# 9250.net
KiCad netlist of a schematic drawn in Altium Designer
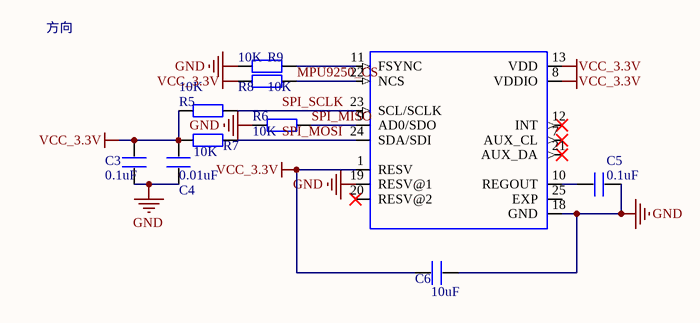
[diagram p0: 9250.SchDoc]

(export (version "E")
  (design (tool "Eeschema 10.0.6"))
  (components
    (comp (ref "C3") (value "0.1uF") (footprint "0805") (libsource (lib "OLED模块封装库") (part "C")))
    (comp (ref "C4") (value "0.01uF") (footprint "0805") (libsource (lib "OLED模块封装库") (part "C")))
    (comp (ref "C5") (value "0.1uF") (footprint "0805") (libsource (lib "OLED模块封装库") (part "C")))
    (comp (ref "C6") (value "10uF") (footprint "0805") (libsource (lib "OLED模块封装库") (part "C")))
    (comp (ref "R5")
      (value "10K")
      (footprint "3.5TFTLCD封装库:0805")
      (description "Resistor")
      (fields (field (name "Comment") "Res2") (field (name "PUBLISHER") "Altium Limited"))
      (libsource (lib "Miscellaneous Devices") (part "Res2"))
    )
    (comp (ref "R6")
      (value "10K")
      (footprint "3.5TFTLCD封装库:0805")
      (description "Resistor")
      (fields (field (name "Comment") "Res2") (field (name "PUBLISHER") "Altium Limited"))
      (libsource (lib "") (part "Res2_1"))
    )
    (comp (ref "R7")
      (value "10K")
      (footprint "3.5TFTLCD封装库:0805")
      (description "Resistor")
      (fields (field (name "Comment") "Res2") (field (name "PUBLISHER") "Altium Limited"))
      (libsource (lib "Miscellaneous Devices") (part "Res2"))
    )
    (comp (ref "R8")
      (value "10K")
      (footprint "3.5TFTLCD封装库:0805")
      (description "Resistor")
      (fields (field (name "Comment") "Res2") (field (name "PUBLISHER") "Altium Limited"))
      (libsource (lib "Miscellaneous Devices") (part "Res2"))
    )
    (comp (ref "R9")
      (value "10K")
      (footprint "3.5TFTLCD封装库:0805")
      (description "Resistor")
      (fields (field (name "Comment") "Res2") (field (name "PUBLISHER") "Altium Limited"))
      (libsource (lib "Miscellaneous Devices") (part "Res2"))
    )
    (comp (ref "U9250")
      (value "MPU-9250")
      (footprint "QFN40P300X300X105-25N")
      (libsource (lib "MPU-9250") (part "MPU-9250"))
    )
  )
  (nets
    (net (code "1") (name "/MPU9250_CS") (class "Default")
      (node (ref "R8") (pin "2") (pinfunction "2_2") (pintype "passive"))
      (node (ref "U9250") (pin "22") (pinfunction "NCS_22") (pintype "input"))
    )
    (net (code "2") (name "/SPI_MISO") (class "Default")
      (node (ref "R6") (pin "1") (pinfunction "1_1") (pintype "passive"))
      (node (ref "U9250") (pin "9") (pinfunction "AD0/SDO_9") (pintype "bidirectional"))
    )
    (net (code "3") (name "/SPI_MOSI") (class "Default")
      (node (ref "R7") (pin "2") (pinfunction "2_2") (pintype "passive"))
      (node (ref "U9250") (pin "24") (pinfunction "SDA/SDI_24") (pintype "bidirectional"))
    )
    (net (code "4") (name "/SPI_SCLK") (class "Default")
      (node (ref "R5") (pin "2") (pinfunction "2_2") (pintype "passive"))
      (node (ref "U9250") (pin "23") (pinfunction "SCL/SCLK_23") (pintype "input"))
    )
    (net (code "5") (name "GND") (class "Default")
      (node (ref "C3") (pin "1") (pintype "passive"))
      (node (ref "C4") (pin "1") (pintype "passive"))
      (node (ref "C5") (pin "1") (pintype "passive"))
      (node (ref "C6") (pin "1") (pintype "passive"))
      (node (ref "R6") (pin "2") (pinfunction "2_2") (pintype "passive"))
      (node (ref "R9") (pin "1") (pinfunction "1_1") (pintype "passive"))
      (node (ref "U9250") (pin "18") (pinfunction "GND_18") (pintype "power_in"))
      (node (ref "U9250") (pin "19") (pinfunction "RESV@1_19") (pintype "power_in"))
    )
    (net (code "6") (name "Net-(U9250-FSYNC)") (class "Default")
      (node (ref "R9") (pin "2") (pinfunction "2_2") (pintype "passive"))
      (node (ref "U9250") (pin "11") (pinfunction "FSYNC_11") (pintype "input"))
    )
    (net (code "7") (name "Net-(U9250-REGOUT)") (class "Default")
      (node (ref "C5") (pin "2") (pintype "passive"))
      (node (ref "U9250") (pin "10") (pinfunction "REGOUT_10") (pintype "passive"))
    )
    (net (code "8") (name "VCC_3.3V") (class "Default")
      (node (ref "C3") (pin "2") (pintype "passive"))
      (node (ref "C4") (pin "2") (pintype "passive"))
      (node (ref "C6") (pin "2") (pintype "passive"))
      (node (ref "R5") (pin "1") (pinfunction "1_1") (pintype "passive"))
      (node (ref "R7") (pin "1") (pinfunction "1_1") (pintype "passive"))
      (node (ref "R8") (pin "1") (pinfunction "1_1") (pintype "passive"))
      (node (ref "U9250") (pin "1") (pinfunction "RESV_1") (pintype "power_in"))
      (node (ref "U9250") (pin "13") (pinfunction "VDD_13") (pintype "power_in"))
      (node (ref "U9250") (pin "8") (pinfunction "VDDIO_8") (pintype "power_in"))
    )
    (net (code "9") (name "unconnected-(U9250-AUX_CL-Pad7)") (class "Default")
      (node (ref "U9250") (pin "7") (pinfunction "AUX_CL_7") (pintype "output+no_connect"))
    )
    (net (code "10") (name "unconnected-(U9250-AUX_DA-Pad21)") (class "Default")
      (node (ref "U9250") (pin "21") (pinfunction "AUX_DA_21") (pintype "output+no_connect"))
    )
    (net (code "11") (name "unconnected-(U9250-EXP-Pad25)") (class "Default")
      (node (ref "U9250") (pin "25") (pinfunction "EXP_25") (pintype "power_in"))
    )
    (net (code "12") (name "unconnected-(U9250-INT-Pad12)") (class "Default")
      (node (ref "U9250") (pin "12") (pinfunction "INT_12") (pintype "output+no_connect"))
    )
    (net (code "13") (name "unconnected-(U9250-RESV@2-Pad20)") (class "Default")
      (node (ref "U9250") (pin "20") (pinfunction "RESV@2_20") (pintype "power_in+no_connect"))
    )
  )
)
